# 01-POWER.net
KiCad netlist of a schematic drawn in Altium Designer
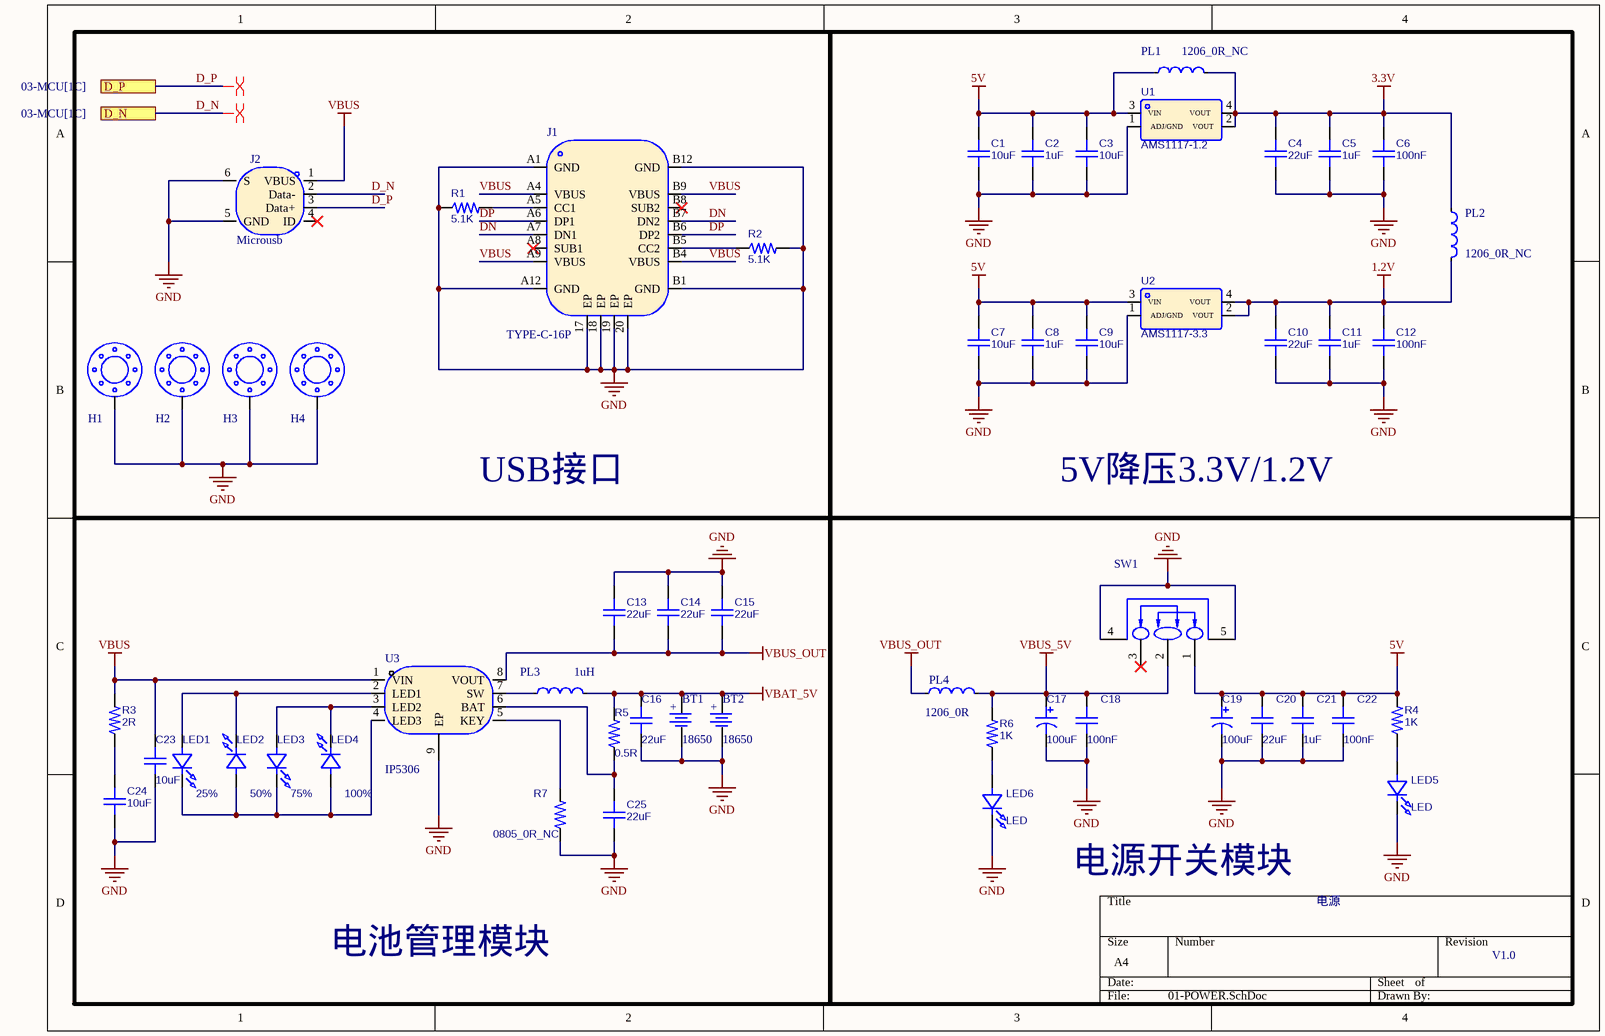
[diagram p0: 01-POWER.SchDoc]

(export (version "E")
  (design (tool "Eeschema 10.0.6"))
  (components
    (comp (ref "BT1")
      (value "18650")
      (footprint "BAT-SMD-18650")
      (description "纽扣电池CR2032-BS-6-1")
      (fields (field (name "MANUFACTURER") "Q&J") (field (name "MANUFACTURER PART") "CR2032-BS-6-1"))
      (libsource (lib "声源跟踪小车原理图库") (part "CR2032"))
    )
    (comp (ref "BT2")
      (value "18650")
      (footprint "BAT-SMD-18650")
      (description "纽扣电池CR2032-BS-6-1")
      (fields (field (name "MANUFACTURER") "Q&J") (field (name "MANUFACTURER PART") "CR2032-BS-6-1"))
      (libsource (lib "声源跟踪小车原理图库") (part "CR2032"))
    )
    (comp (ref "C1")
      (value "10uF")
      (footprint "CAP-SMD-0603")
      (description "贴片电容")
      (fields
        (field (name "BOM_MANUFACTURER PART") "CL03A104KQ3NNNC")
        (field (name "BOM_SUPPLIER PART") "C160831")
        (field (name "CONTRIBUTOR") "LCSC")
      )
      (libsource (lib "声源跟踪小车原理图库") (part "CAP"))
    )
    (comp (ref "C2")
      (value "1uF")
      (footprint "CAP-SMD-0603")
      (description "贴片电容")
      (fields
        (field (name "BOM_MANUFACTURER PART") "CL03A104KQ3NNNC")
        (field (name "BOM_SUPPLIER PART") "C160831")
        (field (name "CONTRIBUTOR") "LCSC")
      )
      (libsource (lib "声源跟踪小车原理图库") (part "CAP"))
    )
    (comp (ref "C3")
      (value "10uF")
      (footprint "CAP-SMD-0603")
      (description "贴片电容")
      (fields
        (field (name "BOM_MANUFACTURER PART") "CL03A104KQ3NNNC")
        (field (name "BOM_SUPPLIER PART") "C160831")
        (field (name "CONTRIBUTOR") "LCSC")
      )
      (libsource (lib "声源跟踪小车原理图库") (part "CAP"))
    )
    (comp (ref "C4")
      (value "22uF")
      (footprint "CAP-SMD-0603")
      (description "贴片电容")
      (fields
        (field (name "BOM_MANUFACTURER PART") "CL03A104KQ3NNNC")
        (field (name "BOM_SUPPLIER PART") "C160831")
        (field (name "CONTRIBUTOR") "LCSC")
      )
      (libsource (lib "声源跟踪小车原理图库") (part "CAP"))
    )
    (comp (ref "C5")
      (value "1uF")
      (footprint "CAP-SMD-0603")
      (description "贴片电容")
      (fields
        (field (name "BOM_MANUFACTURER PART") "CL03A104KQ3NNNC")
        (field (name "BOM_SUPPLIER PART") "C160831")
        (field (name "CONTRIBUTOR") "LCSC")
      )
      (libsource (lib "声源跟踪小车原理图库") (part "CAP"))
    )
    (comp (ref "C6")
      (value "100nF")
      (footprint "CAP-SMD-0603")
      (description "贴片电容")
      (fields
        (field (name "BOM_MANUFACTURER PART") "CL03A104KQ3NNNC")
        (field (name "BOM_SUPPLIER PART") "C160831")
        (field (name "CONTRIBUTOR") "LCSC")
      )
      (libsource (lib "声源跟踪小车原理图库") (part "CAP"))
    )
    (comp (ref "C7")
      (value "10uF")
      (footprint "CAP-SMD-0603")
      (description "贴片电容")
      (fields
        (field (name "BOM_MANUFACTURER PART") "CL03A104KQ3NNNC")
        (field (name "BOM_SUPPLIER PART") "C160831")
        (field (name "CONTRIBUTOR") "LCSC")
      )
      (libsource (lib "声源跟踪小车原理图库") (part "CAP"))
    )
    (comp (ref "C8")
      (value "1uF")
      (footprint "CAP-SMD-0603")
      (description "贴片电容")
      (fields
        (field (name "BOM_MANUFACTURER PART") "CL03A104KQ3NNNC")
        (field (name "BOM_SUPPLIER PART") "C160831")
        (field (name "CONTRIBUTOR") "LCSC")
      )
      (libsource (lib "声源跟踪小车原理图库") (part "CAP"))
    )
    (comp (ref "C9")
      (value "10uF")
      (footprint "CAP-SMD-0603")
      (description "贴片电容")
      (fields
        (field (name "BOM_MANUFACTURER PART") "CL03A104KQ3NNNC")
        (field (name "BOM_SUPPLIER PART") "C160831")
        (field (name "CONTRIBUTOR") "LCSC")
      )
      (libsource (lib "声源跟踪小车原理图库") (part "CAP"))
    )
    (comp (ref "C10")
      (value "22uF")
      (footprint "CAP-SMD-0603")
      (description "贴片电容")
      (fields
        (field (name "BOM_MANUFACTURER PART") "CL03A104KQ3NNNC")
        (field (name "BOM_SUPPLIER PART") "C160831")
        (field (name "CONTRIBUTOR") "LCSC")
      )
      (libsource (lib "声源跟踪小车原理图库") (part "CAP"))
    )
    (comp (ref "C11")
      (value "1uF")
      (footprint "CAP-SMD-0603")
      (description "贴片电容")
      (fields
        (field (name "BOM_MANUFACTURER PART") "CL03A104KQ3NNNC")
        (field (name "BOM_SUPPLIER PART") "C160831")
        (field (name "CONTRIBUTOR") "LCSC")
      )
      (libsource (lib "声源跟踪小车原理图库") (part "CAP"))
    )
    (comp (ref "C12")
      (value "100nF")
      (footprint "CAP-SMD-0603")
      (description "贴片电容")
      (fields
        (field (name "BOM_MANUFACTURER PART") "CL03A104KQ3NNNC")
        (field (name "BOM_SUPPLIER PART") "C160831")
        (field (name "CONTRIBUTOR") "LCSC")
      )
      (libsource (lib "声源跟踪小车原理图库") (part "CAP"))
    )
    (comp (ref "C13")
      (value "22uF")
      (footprint "CAP-SMD-0603")
      (description "贴片电容")
      (fields
        (field (name "BOM_MANUFACTURER PART") "CL03A104KQ3NNNC")
        (field (name "BOM_SUPPLIER PART") "C160831")
        (field (name "CONTRIBUTOR") "LCSC")
      )
      (libsource (lib "声源跟踪小车原理图库") (part "CAP"))
    )
    (comp (ref "C14")
      (value "22uF")
      (footprint "CAP-SMD-0603")
      (description "贴片电容")
      (fields
        (field (name "BOM_MANUFACTURER PART") "CL03A104KQ3NNNC")
        (field (name "BOM_SUPPLIER PART") "C160831")
        (field (name "CONTRIBUTOR") "LCSC")
      )
      (libsource (lib "声源跟踪小车原理图库") (part "CAP"))
    )
    (comp (ref "C15")
      (value "22uF")
      (footprint "CAP-SMD-0603")
      (description "贴片电容")
      (fields
        (field (name "BOM_MANUFACTURER PART") "CL03A104KQ3NNNC")
        (field (name "BOM_SUPPLIER PART") "C160831")
        (field (name "CONTRIBUTOR") "LCSC")
      )
      (libsource (lib "声源跟踪小车原理图库") (part "CAP"))
    )
    (comp (ref "C16")
      (value "22uF")
      (footprint "CAP-SMD-0603")
      (description "贴片电容")
      (fields
        (field (name "BOM_MANUFACTURER PART") "CL03A104KQ3NNNC")
        (field (name "BOM_SUPPLIER PART") "C160831")
        (field (name "CONTRIBUTOR") "LCSC")
      )
      (libsource (lib "声源跟踪小车原理图库") (part "CAP"))
    )
    (comp (ref "C17")
      (value "100uF")
      (footprint "CAPA-TH-5020-P2.0")
      (description "电解电容")
      (fields
        (field (name "BOM_MANUFACTURER PART") "普通黑色470UF 50V")
        (field (name "BOM_SUPPLIER PART") "C34642")
      )
      (libsource (lib "声源跟踪小车原理图库") (part "CAPA"))
    )
    (comp (ref "C18")
      (value "100nF")
      (footprint "CAP-SMD-0603")
      (description "贴片电容")
      (fields
        (field (name "BOM_MANUFACTURER PART") "CL03A104KQ3NNNC")
        (field (name "BOM_SUPPLIER PART") "C160831")
        (field (name "CONTRIBUTOR") "LCSC")
      )
      (libsource (lib "声源跟踪小车原理图库") (part "CAP"))
    )
    (comp (ref "C19")
      (value "100uF")
      (footprint "CAPA-TH-5020-P2.0")
      (description "电解电容")
      (fields
        (field (name "BOM_MANUFACTURER PART") "普通黑色470UF 50V")
        (field (name "BOM_SUPPLIER PART") "C34642")
      )
      (libsource (lib "声源跟踪小车原理图库") (part "CAPA"))
    )
    (comp (ref "C20")
      (value "22uF")
      (footprint "CAP-SMD-0603")
      (description "贴片电容")
      (fields
        (field (name "BOM_MANUFACTURER PART") "CL03A104KQ3NNNC")
        (field (name "BOM_SUPPLIER PART") "C160831")
        (field (name "CONTRIBUTOR") "LCSC")
      )
      (libsource (lib "声源跟踪小车原理图库") (part "CAP"))
    )
    (comp (ref "C21")
      (value "1uF")
      (footprint "CAP-SMD-0603")
      (description "贴片电容")
      (fields
        (field (name "BOM_MANUFACTURER PART") "CL03A104KQ3NNNC")
        (field (name "BOM_SUPPLIER PART") "C160831")
        (field (name "CONTRIBUTOR") "LCSC")
      )
      (libsource (lib "声源跟踪小车原理图库") (part "CAP"))
    )
    (comp (ref "C22")
      (value "100nF")
      (footprint "CAP-SMD-0603")
      (description "贴片电容")
      (fields
        (field (name "BOM_MANUFACTURER PART") "CL03A104KQ3NNNC")
        (field (name "BOM_SUPPLIER PART") "C160831")
        (field (name "CONTRIBUTOR") "LCSC")
      )
      (libsource (lib "声源跟踪小车原理图库") (part "CAP"))
    )
    (comp (ref "C23")
      (value "10uF")
      (footprint "CAP-SMD-0603")
      (description "贴片电容")
      (fields
        (field (name "BOM_MANUFACTURER PART") "CL03A104KQ3NNNC")
        (field (name "BOM_SUPPLIER PART") "C160831")
        (field (name "CONTRIBUTOR") "LCSC")
      )
      (libsource (lib "声源跟踪小车原理图库") (part "CAP"))
    )
    (comp (ref "C24")
      (value "10uF")
      (footprint "CAP-SMD-0603")
      (description "贴片电容")
      (fields
        (field (name "BOM_MANUFACTURER PART") "CL03A104KQ3NNNC")
        (field (name "BOM_SUPPLIER PART") "C160831")
        (field (name "CONTRIBUTOR") "LCSC")
      )
      (libsource (lib "声源跟踪小车原理图库") (part "CAP"))
    )
    (comp (ref "C25")
      (value "22uF")
      (footprint "CAP-SMD-0603")
      (description "贴片电容")
      (fields
        (field (name "BOM_MANUFACTURER PART") "CL03A104KQ3NNNC")
        (field (name "BOM_SUPPLIER PART") "C160831")
        (field (name "CONTRIBUTOR") "LCSC")
      )
      (libsource (lib "声源跟踪小车原理图库") (part "CAP"))
    )
    (comp (ref "H1")
      (value "M3")
      (footprint "M3-5030-0.3")
      (description "M3螺丝孔")
      (libsource (lib "声源跟踪小车原理图库") (part "M3"))
    )
    (comp (ref "H2")
      (value "M3")
      (footprint "M3-5030-0.3")
      (description "M3螺丝孔")
      (libsource (lib "声源跟踪小车原理图库") (part "M3"))
    )
    (comp (ref "H3")
      (value "M3")
      (footprint "M3-5030-0.3")
      (description "M3螺丝孔")
      (libsource (lib "声源跟踪小车原理图库") (part "M3"))
    )
    (comp (ref "H4")
      (value "M3")
      (footprint "M3-5030-0.3")
      (description "M3螺丝孔")
      (libsource (lib "声源跟踪小车原理图库") (part "M3"))
    )
    (comp (ref "J1")
      (value "TYPE-C-16P")
      (footprint "TYPE-C-SMD-16P")
      (description "TYPE-C-16pin")
      (fields
        (field (name "MANUFACTURER") "kinghelm(金航标)")
        (field (name "MANUFACTURER PART") "KH-TYPE-C-16P")
      )
      (libsource (lib "声源跟踪小车原理图库") (part "TYPE-C-16P"))
    )
    (comp (ref "J2")
      (value "Microusb")
      (footprint "Microusb-SMD-5P")
      (description "安卓阶梯型USB接口")
      (fields (field (name "MANUFACTURER") "Amphenol") (field (name "MANUFACTURER PART") "10118194-0001LF"))
      (libsource (lib "声源跟踪小车原理图库") (part "Microusb-5P"))
    )
    (comp (ref "LED1")
      (value "25%")
      (footprint "LED-SMD-0805")
      (description "LED灯,发光二极管")
      (fields
        (field (name "BOM_SUPPLIER PART") "C434447")
        (field (name "BOM_MANUFACTURER PART") "SZYY0402B")
        (field (name "CONTRIBUTOR") "LCSC")
      )
      (libsource (lib "声源跟踪小车原理图库") (part "LED"))
    )
    (comp (ref "LED2")
      (value "50%")
      (footprint "LED-SMD-0805")
      (description "LED灯,发光二极管")
      (fields
        (field (name "BOM_SUPPLIER PART") "C434447")
        (field (name "BOM_MANUFACTURER PART") "SZYY0402B")
        (field (name "CONTRIBUTOR") "LCSC")
      )
      (libsource (lib "声源跟踪小车原理图库") (part "LED"))
    )
    (comp (ref "LED3")
      (value "75%")
      (footprint "LED-SMD-0805")
      (description "LED灯,发光二极管")
      (fields
        (field (name "BOM_SUPPLIER PART") "C434447")
        (field (name "BOM_MANUFACTURER PART") "SZYY0402B")
        (field (name "CONTRIBUTOR") "LCSC")
      )
      (libsource (lib "声源跟踪小车原理图库") (part "LED"))
    )
    (comp (ref "LED4")
      (value "100%")
      (footprint "LED-SMD-0805")
      (description "LED灯,发光二极管")
      (fields
        (field (name "BOM_SUPPLIER PART") "C434447")
        (field (name "BOM_MANUFACTURER PART") "SZYY0402B")
        (field (name "CONTRIBUTOR") "LCSC")
      )
      (libsource (lib "声源跟踪小车原理图库") (part "LED"))
    )
    (comp (ref "LED5")
      (value "LED")
      (footprint "LED-SMD-0805")
      (description "LED灯,发光二极管")
      (fields
        (field (name "BOM_SUPPLIER PART") "C434447")
        (field (name "BOM_MANUFACTURER PART") "SZYY0402B")
        (field (name "CONTRIBUTOR") "LCSC")
      )
      (libsource (lib "声源跟踪小车原理图库") (part "LED"))
    )
    (comp (ref "LED6")
      (value "LED")
      (footprint "LED-SMD-0805")
      (description "LED灯,发光二极管")
      (fields
        (field (name "BOM_SUPPLIER PART") "C434447")
        (field (name "BOM_MANUFACTURER PART") "SZYY0402B")
        (field (name "CONTRIBUTOR") "LCSC")
      )
      (libsource (lib "声源跟踪小车原理图库") (part "LED"))
    )
    (comp (ref "PL1")
      (value "1206_0R_NC")
      (footprint "PL-SMD_4.4X4.2-P3.7")
      (description "电感")
      (fields (field (name "MANUFACTURER") "Sunlord(顺络)") (field (name "MANUFACTURER PART") "GZ1608D121TF"))
      (libsource (lib "声源跟踪小车原理图库") (part "PL-IND"))
    )
    (comp (ref "PL2")
      (value "1206_0R_NC")
      (footprint "PL-SMD_4.4X4.2-P3.7")
      (description "电感")
      (fields (field (name "MANUFACTURER") "Sunlord(顺络)") (field (name "MANUFACTURER PART") "GZ1608D121TF"))
      (libsource (lib "声源跟踪小车原理图库") (part "PL-IND"))
    )
    (comp (ref "PL3")
      (value "1uH")
      (footprint "PL-SMD_4.4X4.2-P3.7")
      (description "电感")
      (fields (field (name "MANUFACTURER") "Sunlord(顺络)") (field (name "MANUFACTURER PART") "GZ1608D121TF"))
      (libsource (lib "声源跟踪小车原理图库") (part "PL-IND"))
    )
    (comp (ref "PL4")
      (value "1206_0R")
      (footprint "PL-SMD_4.4X4.2-P3.7")
      (description "电感")
      (fields (field (name "MANUFACTURER") "Sunlord(顺络)") (field (name "MANUFACTURER PART") "GZ1608D121TF"))
      (libsource (lib "声源跟踪小车原理图库") (part "PL-IND"))
    )
    (comp (ref "R1")
      (value "5.1K")
      (footprint "RES-SMD-0603")
      (description "贴片电阻")
      (fields
        (field (name "BOM_SUPPLIER PART") "C118966")
        (field (name "BOM_MANUFACTURER PART") "3362P-1-104")
        (field (name "CONTRIBUTOR") "LCSC")
      )
      (libsource (lib "声源跟踪小车原理图库") (part "RES"))
    )
    (comp (ref "R2")
      (value "5.1K")
      (footprint "RES-SMD-0603")
      (description "贴片电阻")
      (fields
        (field (name "BOM_SUPPLIER PART") "C118966")
        (field (name "BOM_MANUFACTURER PART") "3362P-1-104")
        (field (name "CONTRIBUTOR") "LCSC")
      )
      (libsource (lib "声源跟踪小车原理图库") (part "RES"))
    )
    (comp (ref "R3")
      (value "2R")
      (footprint "RES-SMD-0603")
      (description "贴片电阻")
      (fields
        (field (name "BOM_SUPPLIER PART") "C118966")
        (field (name "BOM_MANUFACTURER PART") "3362P-1-104")
        (field (name "CONTRIBUTOR") "LCSC")
      )
      (libsource (lib "声源跟踪小车原理图库") (part "RES"))
    )
    (comp (ref "R4")
      (value "1K")
      (footprint "RES-SMD-0603")
      (description "贴片电阻")
      (fields
        (field (name "BOM_SUPPLIER PART") "C118966")
        (field (name "BOM_MANUFACTURER PART") "3362P-1-104")
        (field (name "CONTRIBUTOR") "LCSC")
      )
      (libsource (lib "声源跟踪小车原理图库") (part "RES"))
    )
    (comp (ref "R5")
      (value "0.5R")
      (footprint "RES-SMD-0603")
      (description "贴片电阻")
      (fields
        (field (name "BOM_SUPPLIER PART") "C118966")
        (field (name "BOM_MANUFACTURER PART") "3362P-1-104")
        (field (name "CONTRIBUTOR") "LCSC")
      )
      (libsource (lib "声源跟踪小车原理图库") (part "RES"))
    )
    (comp (ref "R6")
      (value "1K")
      (footprint "RES-SMD-0603")
      (description "贴片电阻")
      (fields
        (field (name "BOM_SUPPLIER PART") "C118966")
        (field (name "BOM_MANUFACTURER PART") "3362P-1-104")
        (field (name "CONTRIBUTOR") "LCSC")
      )
      (libsource (lib "声源跟踪小车原理图库") (part "RES"))
    )
    (comp (ref "R7")
      (value "0805_0R_NC")
      (footprint "RES-SMD-0603")
      (description "贴片电阻")
      (fields
        (field (name "BOM_SUPPLIER PART") "C118966")
        (field (name "BOM_MANUFACTURER PART") "3362P-1-104")
        (field (name "CONTRIBUTOR") "LCSC")
      )
      (libsource (lib "声源跟踪小车原理图库") (part "RES"))
    )
    (comp (ref "SW1")
      (value "SS-12D11G5")
      (footprint "SW-TH-D-P4.8")
      (description "额定电流(DC)：3A 额定电压(DC)：125V 额定电流(AC)：3A 额定电压(AC)：125V")
      (fields (field (name "MANUFACTURER") "XKB Connectivity(中国星坤)"))
      (libsource (lib "声源跟踪小车原理图库") (part "SW-D-3P"))
    )
    (comp (ref "U1")
      (value "AMS1117-1.2")
      (footprint "SOT-223-4-LP5.7-P2.3")
      (description "稳压器芯片")
      (fields
        (field (name "BOM_SUPPLIER PART") "C2718490")
        (field (name "BOM_MANUFACTURER PART") "AMS1117-5.0")
        (field (name "CONTRIBUTOR") "LCSC")
      )
      (libsource (lib "声源跟踪小车原理图库") (part "AMS1117-5.0"))
    )
    (comp (ref "U2")
      (value "AMS1117-3.3")
      (footprint "SOT-223-4-LP5.7-P2.3")
      (description "稳压器芯片")
      (fields
        (field (name "BOM_SUPPLIER PART") "C2718490")
        (field (name "BOM_MANUFACTURER PART") "AMS1117-5.0")
        (field (name "CONTRIBUTOR") "LCSC")
      )
      (libsource (lib "声源跟踪小车原理图库") (part "AMS1117-5.0_1"))
    )
    (comp (ref "U3")
      (value "IP5306")
      (footprint "ESOP-8-LP5.3-P1.27")
      (description "充电电池的类型:-;电池单元组数:-;最大充电电流:-;充满的电池组电压:-;最大供应电压:-;")
      (fields (field (name "MANUFACTURER") "INJOINIC(英集芯)"))
      (libsource (lib "声源跟踪小车原理图库") (part "IP5306"))
    )
  )
  (nets
    (net (code "1") (name "/DN") (class "Default")
      (node (ref "J1") (pin "A7") (pinfunction "DN1_A7") (pintype "passive"))
      (node (ref "J1") (pin "B7") (pinfunction "DN2_B7") (pintype "passive"))
    )
    (net (code "2") (name "/DP") (class "Default")
      (node (ref "J1") (pin "A6") (pinfunction "DP1_A6") (pintype "passive"))
      (node (ref "J1") (pin "B6") (pinfunction "DP2_B6") (pintype "passive"))
    )
    (net (code "3") (name "/D_N") (class "Default")
      (node (ref "J2") (pin "2") (pinfunction "Data-_2") (pintype "passive"))
    )
    (net (code "4") (name "/D_P") (class "Default")
      (node (ref "J2") (pin "3") (pinfunction "Data+_3") (pintype "passive"))
    )
    (net (code "5") (name "1.2V") (class "Default")
      (node (ref "C10") (pin "2") (pinfunction "2_2") (pintype "passive"))
      (node (ref "C11") (pin "2") (pinfunction "2_2") (pintype "passive"))
      (node (ref "C12") (pin "2") (pinfunction "2_2") (pintype "passive"))
      (node (ref "PL2") (pin "2") (pinfunction "2_2") (pintype "passive"))
      (node (ref "U2") (pin "2") (pinfunction "VOUT_2") (pintype "passive"))
      (node (ref "U2") (pin "4") (pinfunction "VOUT_4") (pintype "passive"))
    )
    (net (code "6") (name "3.3V") (class "Default")
      (node (ref "C4") (pin "2") (pinfunction "2_2") (pintype "passive"))
      (node (ref "C5") (pin "2") (pinfunction "2_2") (pintype "passive"))
      (node (ref "C6") (pin "2") (pinfunction "2_2") (pintype "passive"))
      (node (ref "PL1") (pin "2") (pinfunction "2_2") (pintype "passive"))
      (node (ref "PL2") (pin "1") (pinfunction "1_1") (pintype "passive"))
      (node (ref "U1") (pin "2") (pinfunction "VOUT_2") (pintype "passive"))
      (node (ref "U1") (pin "4") (pinfunction "VOUT_4") (pintype "passive"))
    )
    (net (code "7") (name "5V") (class "Default")
      (node (ref "C1") (pin "2") (pinfunction "2_2") (pintype "passive"))
      (node (ref "C19") (pin "1") (pinfunction "1_1") (pintype "passive"))
      (node (ref "C2") (pin "2") (pinfunction "2_2") (pintype "passive"))
      (node (ref "C20") (pin "2") (pinfunction "2_2") (pintype "passive"))
      (node (ref "C21") (pin "2") (pinfunction "2_2") (pintype "passive"))
      (node (ref "C22") (pin "2") (pinfunction "2_2") (pintype "passive"))
      (node (ref "C3") (pin "2") (pinfunction "2_2") (pintype "passive"))
      (node (ref "C7") (pin "2") (pinfunction "2_2") (pintype "passive"))
      (node (ref "C8") (pin "2") (pinfunction "2_2") (pintype "passive"))
      (node (ref "C9") (pin "2") (pinfunction "2_2") (pintype "passive"))
      (node (ref "PL1") (pin "1") (pinfunction "1_1") (pintype "passive"))
      (node (ref "R4") (pin "2") (pinfunction "2_2") (pintype "passive"))
      (node (ref "SW1") (pin "1") (pinfunction "1_1") (pintype "passive"))
      (node (ref "U1") (pin "3") (pinfunction "VIN_3") (pintype "passive"))
      (node (ref "U2") (pin "3") (pinfunction "VIN_3") (pintype "passive"))
    )
    (net (code "8") (name "GND") (class "Default")
      (node (ref "BT1") (pin "2") (pinfunction "+_2") (pintype "passive"))
      (node (ref "BT2") (pin "2") (pinfunction "+_2") (pintype "passive"))
      (node (ref "C1") (pin "1") (pinfunction "1_1") (pintype "passive"))
      (node (ref "C10") (pin "1") (pinfunction "1_1") (pintype "passive"))
      (node (ref "C11") (pin "1") (pinfunction "1_1") (pintype "passive"))
      (node (ref "C12") (pin "1") (pinfunction "1_1") (pintype "passive"))
      (node (ref "C13") (pin "2") (pinfunction "2_2") (pintype "passive"))
      (node (ref "C14") (pin "2") (pinfunction "2_2") (pintype "passive"))
      (node (ref "C15") (pin "2") (pinfunction "2_2") (pintype "passive"))
      (node (ref "C16") (pin "1") (pinfunction "1_1") (pintype "passive"))
      (node (ref "C17") (pin "2") (pinfunction "2_2") (pintype "passive"))
      (node (ref "C18") (pin "1") (pinfunction "1_1") (pintype "passive"))
      (node (ref "C19") (pin "2") (pinfunction "2_2") (pintype "passive"))
      (node (ref "C2") (pin "1") (pinfunction "1_1") (pintype "passive"))
      (node (ref "C20") (pin "1") (pinfunction "1_1") (pintype "passive"))
      (node (ref "C21") (pin "1") (pinfunction "1_1") (pintype "passive"))
      (node (ref "C22") (pin "1") (pinfunction "1_1") (pintype "passive"))
      (node (ref "C23") (pin "1") (pinfunction "1_1") (pintype "passive"))
      (node (ref "C24") (pin "1") (pinfunction "1_1") (pintype "passive"))
      (node (ref "C25") (pin "1") (pinfunction "1_1") (pintype "passive"))
      (node (ref "C3") (pin "1") (pinfunction "1_1") (pintype "passive"))
      (node (ref "C4") (pin "1") (pinfunction "1_1") (pintype "passive"))
      (node (ref "C5") (pin "1") (pinfunction "1_1") (pintype "passive"))
      (node (ref "C6") (pin "1") (pinfunction "1_1") (pintype "passive"))
      (node (ref "C7") (pin "1") (pinfunction "1_1") (pintype "passive"))
      (node (ref "C8") (pin "1") (pinfunction "1_1") (pintype "passive"))
      (node (ref "C9") (pin "1") (pinfunction "1_1") (pintype "passive"))
      (node (ref "H1") (pin "1") (pinfunction "1_1") (pintype "passive"))
      (node (ref "H2") (pin "1") (pinfunction "1_1") (pintype "passive"))
      (node (ref "H3") (pin "1") (pinfunction "1_1") (pintype "passive"))
      (node (ref "H4") (pin "1") (pinfunction "1_1") (pintype "passive"))
      (node (ref "J1") (pin "17") (pinfunction "EP_17") (pintype "passive"))
      (node (ref "J1") (pin "18") (pinfunction "EP_18") (pintype "passive"))
      (node (ref "J1") (pin "19") (pinfunction "EP_19") (pintype "passive"))
      (node (ref "J1") (pin "20") (pinfunction "EP_20") (pintype "passive"))
      (node (ref "J1") (pin "A1") (pinfunction "GND_A1") (pintype "passive"))
      (node (ref "J1") (pin "A12") (pinfunction "GND_A12") (pintype "passive"))
      (node (ref "J1") (pin "B1") (pinfunction "GND_B1") (pintype "passive"))
      (node (ref "J1") (pin "B12") (pinfunction "GND_B12") (pintype "passive"))
      (node (ref "J2") (pin "5") (pinfunction "GND_5") (pintype "passive"))
      (node (ref "J2") (pin "6") (pinfunction "S_6") (pintype "passive"))
      (node (ref "LED5") (pin "2") (pinfunction "K_2") (pintype "passive"))
      (node (ref "LED6") (pin "2") (pinfunction "K_2") (pintype "passive"))
      (node (ref "R1") (pin "1") (pinfunction "1_1") (pintype "passive"))
      (node (ref "R2") (pin "2") (pinfunction "2_2") (pintype "passive"))
      (node (ref "R7") (pin "1") (pinfunction "1_1") (pintype "passive"))
      (node (ref "SW1") (pin "4") (pinfunction "4_4") (pintype "passive"))
      (node (ref "SW1") (pin "5") (pinfunction "5_5") (pintype "passive"))
      (node (ref "U1") (pin "1") (pinfunction "ADJ/GND_1") (pintype "passive"))
      (node (ref "U2") (pin "1") (pinfunction "ADJ/GND_1") (pintype "passive"))
      (node (ref "U3") (pin "9") (pinfunction "EP_9") (pintype "passive"))
    )
    (net (code "9") (name "Net-(C24-Pad2)") (class "Default")
      (node (ref "C24") (pin "2") (pinfunction "2_2") (pintype "passive"))
      (node (ref "R3") (pin "1") (pinfunction "1_1") (pintype "passive"))
    )
    (net (code "10") (name "Net-(J1-CC1)") (class "Default")
      (node (ref "J1") (pin "A5") (pinfunction "CC1_A5") (pintype "passive"))
      (node (ref "R1") (pin "2") (pinfunction "2_2") (pintype "passive"))
    )
    (net (code "11") (name "Net-(J1-CC2)") (class "Default")
      (node (ref "J1") (pin "B5") (pinfunction "CC2_B5") (pintype "passive"))
      (node (ref "R2") (pin "1") (pinfunction "1_1") (pintype "passive"))
    )
    (net (code "12") (name "Net-(LED1-A)") (class "Default")
      (node (ref "LED1") (pin "1") (pinfunction "A_1") (pintype "passive"))
      (node (ref "LED2") (pin "2") (pinfunction "K_2") (pintype "passive"))
      (node (ref "U3") (pin "2") (pinfunction "LED1_2") (pintype "passive"))
    )
    (net (code "13") (name "Net-(LED1-K)") (class "Default")
      (node (ref "LED1") (pin "2") (pinfunction "K_2") (pintype "passive"))
      (node (ref "LED2") (pin "1") (pinfunction "A_1") (pintype "passive"))
      (node (ref "LED3") (pin "2") (pinfunction "K_2") (pintype "passive"))
      (node (ref "LED4") (pin "1") (pinfunction "A_1") (pintype "passive"))
      (node (ref "U3") (pin "4") (pinfunction "LED3_4") (pintype "passive"))
    )
    (net (code "14") (name "Net-(LED3-A)") (class "Default")
      (node (ref "LED3") (pin "1") (pinfunction "A_1") (pintype "passive"))
      (node (ref "LED4") (pin "2") (pinfunction "K_2") (pintype "passive"))
      (node (ref "U3") (pin "3") (pinfunction "LED2_3") (pintype "passive"))
    )
    (net (code "15") (name "Net-(LED5-A)") (class "Default")
      (node (ref "LED5") (pin "1") (pinfunction "A_1") (pintype "passive"))
      (node (ref "R4") (pin "1") (pinfunction "1_1") (pintype "passive"))
    )
    (net (code "16") (name "Net-(LED6-A)") (class "Default")
      (node (ref "LED6") (pin "1") (pinfunction "A_1") (pintype "passive"))
      (node (ref "R6") (pin "1") (pinfunction "1_1") (pintype "passive"))
    )
    (net (code "17") (name "Net-(U3-BAT)") (class "Default")
      (node (ref "C25") (pin "2") (pinfunction "2_2") (pintype "passive"))
      (node (ref "R5") (pin "1") (pinfunction "1_1") (pintype "passive"))
      (node (ref "U3") (pin "6") (pinfunction "BAT_6") (pintype "passive"))
    )
    (net (code "18") (name "Net-(U3-KEY)") (class "Default")
      (node (ref "R7") (pin "2") (pinfunction "2_2") (pintype "passive"))
      (node (ref "U3") (pin "5") (pinfunction "KEY_5") (pintype "passive"))
    )
    (net (code "19") (name "Net-(U3-SW)") (class "Default")
      (node (ref "PL3") (pin "1") (pinfunction "1_1") (pintype "passive"))
      (node (ref "U3") (pin "7") (pinfunction "SW_7") (pintype "passive"))
    )
    (net (code "20") (name "VBAT_5V") (class "Default")
      (node (ref "BT1") (pin "1") (pinfunction "-_1") (pintype "passive"))
      (node (ref "BT2") (pin "1") (pinfunction "-_1") (pintype "passive"))
      (node (ref "C16") (pin "2") (pinfunction "2_2") (pintype "passive"))
      (node (ref "PL3") (pin "2") (pinfunction "2_2") (pintype "passive"))
      (node (ref "R5") (pin "2") (pinfunction "2_2") (pintype "passive"))
    )
    (net (code "21") (name "VBUS") (class "Default")
      (node (ref "C23") (pin "2") (pinfunction "2_2") (pintype "passive"))
      (node (ref "J1") (pin "A4") (pinfunction "VBUS_A4") (pintype "passive"))
      (node (ref "J1") (pin "A9") (pinfunction "VBUS_A9") (pintype "passive"))
      (node (ref "J1") (pin "B4") (pinfunction "VBUS_B4") (pintype "passive"))
      (node (ref "J1") (pin "B9") (pinfunction "VBUS_B9") (pintype "passive"))
      (node (ref "J2") (pin "1") (pinfunction "VBUS_1") (pintype "passive"))
      (node (ref "R3") (pin "2") (pinfunction "2_2") (pintype "passive"))
      (node (ref "U3") (pin "1") (pinfunction "VIN_1") (pintype "passive"))
    )
    (net (code "22") (name "VBUS_5V") (class "Default")
      (node (ref "C17") (pin "1") (pinfunction "1_1") (pintype "passive"))
      (node (ref "C18") (pin "2") (pinfunction "2_2") (pintype "passive"))
      (node (ref "PL4") (pin "2") (pinfunction "2_2") (pintype "passive"))
      (node (ref "R6") (pin "2") (pinfunction "2_2") (pintype "passive"))
      (node (ref "SW1") (pin "2") (pinfunction "2_2") (pintype "passive"))
    )
    (net (code "23") (name "VBUS_OUT") (class "Default")
      (node (ref "C13") (pin "1") (pinfunction "1_1") (pintype "passive"))
      (node (ref "C14") (pin "1") (pinfunction "1_1") (pintype "passive"))
      (node (ref "C15") (pin "1") (pinfunction "1_1") (pintype "passive"))
      (node (ref "PL4") (pin "1") (pinfunction "1_1") (pintype "passive"))
      (node (ref "U3") (pin "8") (pinfunction "VOUT_8") (pintype "passive"))
    )
    (net (code "24") (name "unconnected-(J1-SUB1-PadA8)") (class "Default")
      (node (ref "J1") (pin "A8") (pinfunction "SUB1_A8") (pintype "passive+no_connect"))
    )
    (net (code "25") (name "unconnected-(J1-SUB2-PadB8)") (class "Default")
      (node (ref "J1") (pin "B8") (pinfunction "SUB2_B8") (pintype "passive+no_connect"))
    )
    (net (code "26") (name "unconnected-(J2-ID-Pad4)") (class "Default")
      (node (ref "J2") (pin "4") (pinfunction "ID_4") (pintype "passive+no_connect"))
    )
    (net (code "27") (name "unconnected-(SW1-Pad3)") (class "Default")
      (node (ref "SW1") (pin "3") (pinfunction "3_3") (pintype "passive+no_connect"))
    )
  )
)
